# GG-CC1101_v1_2.net
KiCad netlist of a schematic drawn in EAGLE
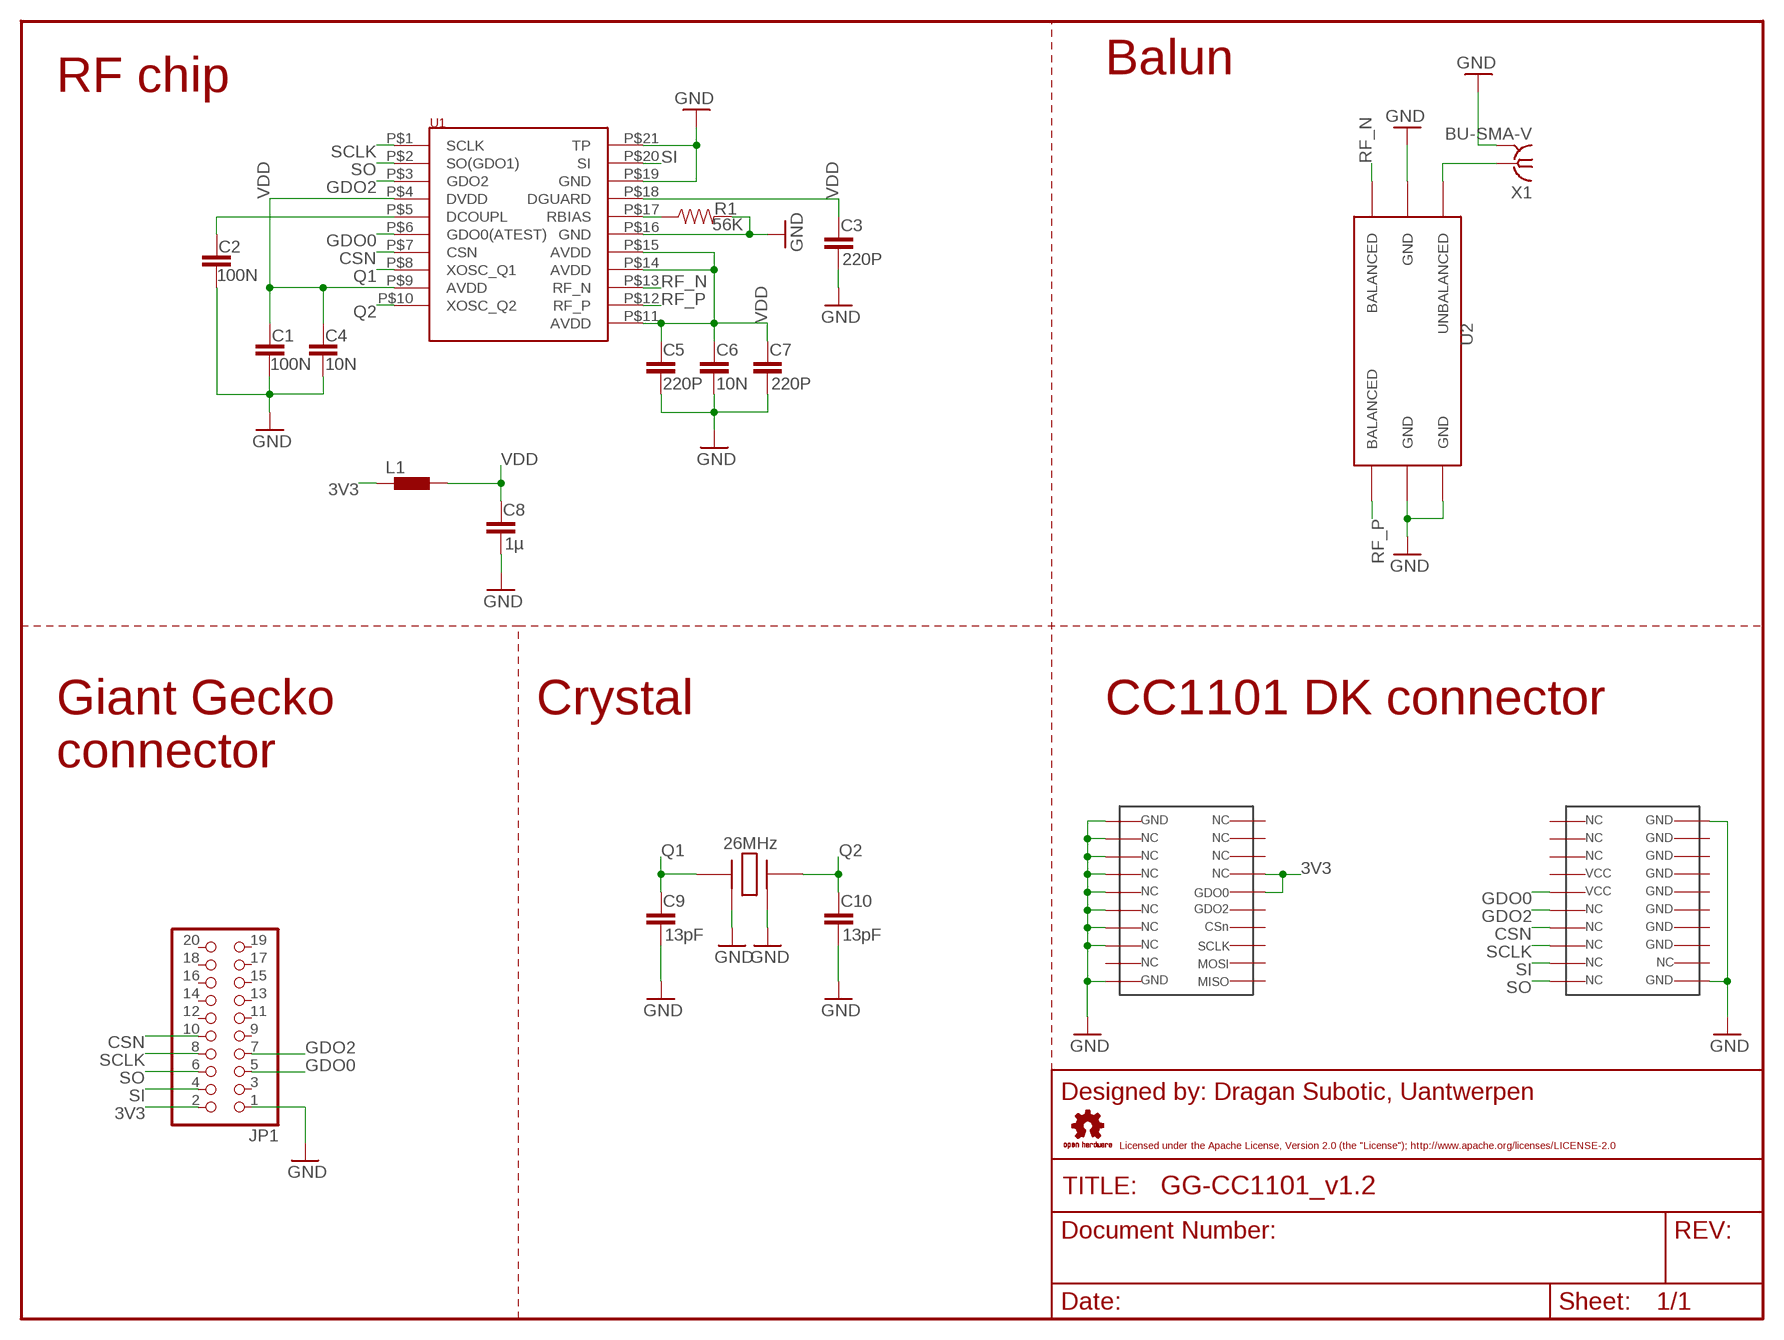
[diagram p0: schematic, sheet 1]

(export (version "E")
  (design (tool "Eeschema 10.0.6"))
  (components
    (comp (ref "C1")
      (value "100N")
      (footprint "eagle-import:0805")
      (libsource (lib "eagle-import") (part "CAP0805"))
    )
    (comp (ref "C2")
      (value "100N")
      (footprint "eagle-import:0805")
      (libsource (lib "eagle-import") (part "CAP0805"))
    )
    (comp (ref "C3")
      (value "220P")
      (footprint "eagle-import:0805")
      (libsource (lib "eagle-import") (part "CAP0805"))
    )
    (comp (ref "C4")
      (value "10N")
      (footprint "eagle-import:0805")
      (libsource (lib "eagle-import") (part "CAP0805"))
    )
    (comp (ref "C5")
      (value "220P")
      (footprint "eagle-import:0805")
      (libsource (lib "eagle-import") (part "CAP0805"))
    )
    (comp (ref "C6")
      (value "10N")
      (footprint "eagle-import:0805")
      (libsource (lib "eagle-import") (part "CAP0805"))
    )
    (comp (ref "C7")
      (value "220P")
      (footprint "eagle-import:0805")
      (libsource (lib "eagle-import") (part "CAP0805"))
    )
    (comp (ref "C8")
      (value "1µ")
      (footprint "eagle-import:0805")
      (libsource (lib "eagle-import") (part "CAP0805"))
    )
    (comp (ref "C9")
      (value "13pF")
      (footprint "eagle-import:0805")
      (libsource (lib "eagle-import") (part "CAP0805"))
    )
    (comp (ref "C10")
      (value "13pF")
      (footprint "eagle-import:0805")
      (libsource (lib "eagle-import") (part "CAP0805"))
    )
    (comp (ref "JP1")
      (value "PINHD-2X10")
      (footprint "eagle-import:2X10")
      (libsource (lib "eagle-import") (part "PINHD-2X10"))
    )
    (comp (ref "L1")
      (value "BLM15HG102SN1")
      (footprint "eagle-import:0402")
      (libsource (lib "eagle-import") (part "BLM15HG102SN1"))
    )
    (comp (ref "Q1")
      (value "XTAL-26MHZ")
      (footprint "eagle-import:XTAL-26MHZ")
      (libsource (lib "eagle-import") (part "XTAL-26MHZ"))
    )
    (comp (ref "R1")
      (value "56K")
      (footprint "eagle-import:0805")
      (libsource (lib "eagle-import") (part "RESISTOR0805-RES"))
    )
    (comp (ref "U$1")
      (value "CC1101-EVAL_KIT")
      (footprint "eagle-import:CC1101-EVAL_KIT")
      (libsource (lib "eagle-import") (part "CC1101-EVAL_KIT"))
    )
    (comp (ref "U1")
      (value "CC1101")
      (footprint "eagle-import:CC1101")
      (libsource (lib "eagle-import") (part "CC1101"))
    )
    (comp (ref "U2")
      (value "BALUN-433MHZ")
      (footprint "eagle-import:BALUN-433MHZ")
      (libsource (lib "eagle-import") (part "BALUN-433MHZ"))
    )
    (comp (ref "X1")
      (value "BU-SMA-V")
      (footprint "eagle-import:BU-SMA-V")
      (libsource (lib "eagle-import") (part "BU-SMA-V"))
    )
  )
  (nets
    (net (code "1") (name "/3V3") (class "Default")
      (node (ref "JP1") (pin "2") (pinfunction "2_2") (pintype "passive"))
      (node (ref "L1") (pin "1") (pinfunction "1_1") (pintype "passive"))
      (node (ref "U$1") (pin "P$14") (pinfunction "P$14_P$14") (pintype "bidirectional"))
      (node (ref "U$1") (pin "P$15") (pinfunction "P$15_P$15") (pintype "bidirectional"))
    )
    (net (code "2") (name "/CSN") (class "Default")
      (node (ref "JP1") (pin "10") (pinfunction "10_10") (pintype "passive"))
      (node (ref "U$1") (pin "P$24") (pinfunction "P$24_P$24") (pintype "bidirectional"))
      (node (ref "U1") (pin "P$7") (pinfunction "CSN_P$7") (pintype "bidirectional"))
    )
    (net (code "3") (name "/GDO0") (class "Default")
      (node (ref "JP1") (pin "5") (pinfunction "5_5") (pintype "passive"))
      (node (ref "U$1") (pin "P$26") (pinfunction "P$26_P$26") (pintype "bidirectional"))
      (node (ref "U1") (pin "P$6") (pinfunction "GDO0(ATEST)_P$6") (pintype "bidirectional"))
    )
    (net (code "4") (name "/GDO2") (class "Default")
      (node (ref "JP1") (pin "7") (pinfunction "7_7") (pintype "passive"))
      (node (ref "U$1") (pin "P$25") (pinfunction "P$25_P$25") (pintype "bidirectional"))
      (node (ref "U1") (pin "P$3") (pinfunction "GDO2_P$3") (pintype "bidirectional"))
    )
    (net (code "5") (name "/Q1") (class "Default")
      (node (ref "C9") (pin "1") (pinfunction "1_1") (pintype "passive"))
      (node (ref "Q1") (pin "P$1") (pinfunction "P$1_P$1") (pintype "bidirectional"))
      (node (ref "U1") (pin "P$8") (pinfunction "XOSC_Q1_P$8") (pintype "bidirectional"))
    )
    (net (code "6") (name "/Q2") (class "Default")
      (node (ref "C10") (pin "1") (pinfunction "1_1") (pintype "passive"))
      (node (ref "Q1") (pin "P$3") (pinfunction "P$3_P$3") (pintype "bidirectional"))
      (node (ref "U1") (pin "P$10") (pinfunction "XOSC_Q2_P$10") (pintype "bidirectional"))
    )
    (net (code "7") (name "/RF_N") (class "Default")
      (node (ref "U1") (pin "P$13") (pinfunction "RF_N_P$13") (pintype "bidirectional"))
      (node (ref "U2") (pin "P$3") (pinfunction "BALANCED_P$3") (pintype "bidirectional"))
    )
    (net (code "8") (name "/RF_P") (class "Default")
      (node (ref "U1") (pin "P$12") (pinfunction "RF_P_P$12") (pintype "bidirectional"))
      (node (ref "U2") (pin "P$4") (pinfunction "BALANCED_P$4") (pintype "bidirectional"))
    )
    (net (code "9") (name "/SCLK") (class "Default")
      (node (ref "JP1") (pin "8") (pinfunction "8_8") (pintype "passive"))
      (node (ref "U$1") (pin "P$23") (pinfunction "P$23_P$23") (pintype "bidirectional"))
      (node (ref "U1") (pin "P$1") (pinfunction "SCLK_P$1") (pintype "bidirectional"))
    )
    (net (code "10") (name "/SI") (class "Default")
      (node (ref "JP1") (pin "4") (pinfunction "4_4") (pintype "passive"))
      (node (ref "U$1") (pin "P$22") (pinfunction "P$22_P$22") (pintype "bidirectional"))
      (node (ref "U1") (pin "P$20") (pinfunction "SI_P$20") (pintype "bidirectional"))
    )
    (net (code "11") (name "/SO") (class "Default")
      (node (ref "JP1") (pin "6") (pinfunction "6_6") (pintype "passive"))
      (node (ref "U$1") (pin "P$21") (pinfunction "P$21_P$21") (pintype "bidirectional"))
      (node (ref "U1") (pin "P$2") (pinfunction "SO(GDO1)_P$2") (pintype "bidirectional"))
    )
    (net (code "12") (name "/VDD") (class "Default")
      (node (ref "C1") (pin "1") (pinfunction "1_1") (pintype "passive"))
      (node (ref "C3") (pin "1") (pinfunction "1_1") (pintype "passive"))
      (node (ref "C4") (pin "1") (pinfunction "1_1") (pintype "passive"))
      (node (ref "C5") (pin "1") (pinfunction "1_1") (pintype "passive"))
      (node (ref "C6") (pin "1") (pinfunction "1_1") (pintype "passive"))
      (node (ref "C7") (pin "1") (pinfunction "1_1") (pintype "passive"))
      (node (ref "C8") (pin "1") (pinfunction "1_1") (pintype "passive"))
      (node (ref "L1") (pin "2") (pinfunction "2_2") (pintype "passive"))
      (node (ref "U1") (pin "P$11") (pinfunction "AVDD_P$11") (pintype "bidirectional"))
      (node (ref "U1") (pin "P$14") (pinfunction "AVDD_P$14") (pintype "bidirectional"))
      (node (ref "U1") (pin "P$15") (pinfunction "AVDD_P$15") (pintype "bidirectional"))
      (node (ref "U1") (pin "P$18") (pinfunction "DGUARD_P$18") (pintype "bidirectional"))
      (node (ref "U1") (pin "P$4") (pinfunction "DVDD_P$4") (pintype "bidirectional"))
      (node (ref "U1") (pin "P$9") (pinfunction "AVDD_P$9") (pintype "bidirectional"))
    )
    (net (code "13") (name "GND") (class "Default")
      (node (ref "C1") (pin "2") (pinfunction "2_2") (pintype "passive"))
      (node (ref "C10") (pin "2") (pinfunction "2_2") (pintype "passive"))
      (node (ref "C2") (pin "2") (pinfunction "2_2") (pintype "passive"))
      (node (ref "C3") (pin "2") (pinfunction "2_2") (pintype "passive"))
      (node (ref "C4") (pin "2") (pinfunction "2_2") (pintype "passive"))
      (node (ref "C5") (pin "2") (pinfunction "2_2") (pintype "passive"))
      (node (ref "C6") (pin "2") (pinfunction "2_2") (pintype "passive"))
      (node (ref "C7") (pin "2") (pinfunction "2_2") (pintype "passive"))
      (node (ref "C8") (pin "2") (pinfunction "2_2") (pintype "passive"))
      (node (ref "C9") (pin "2") (pinfunction "2_2") (pintype "passive"))
      (node (ref "JP1") (pin "1") (pinfunction "1_1") (pintype "passive"))
      (node (ref "Q1") (pin "P$2") (pinfunction "P$2_P$2") (pintype "bidirectional"))
      (node (ref "Q1") (pin "P$4") (pinfunction "P$4_P$4") (pintype "bidirectional"))
      (node (ref "R1") (pin "2") (pinfunction "2_2") (pintype "passive"))
      (node (ref "U$1") (pin "P$1") (pinfunction "P$1_P$1") (pintype "bidirectional"))
      (node (ref "U$1") (pin "P$10") (pinfunction "P$10_P$10") (pintype "bidirectional"))
      (node (ref "U$1") (pin "P$3") (pinfunction "P$3_P$3") (pintype "bidirectional"))
      (node (ref "U$1") (pin "P$31") (pinfunction "P$31_P$31") (pintype "bidirectional"))
      (node (ref "U$1") (pin "P$4") (pinfunction "P$4_P$4") (pintype "bidirectional"))
      (node (ref "U$1") (pin "P$40") (pinfunction "P$40_P$40") (pintype "bidirectional"))
      (node (ref "U$1") (pin "P$5") (pinfunction "P$5_P$5") (pintype "bidirectional"))
      (node (ref "U$1") (pin "P$6") (pinfunction "P$6_P$6") (pintype "bidirectional"))
      (node (ref "U$1") (pin "P$7") (pinfunction "P$7_P$7") (pintype "bidirectional"))
      (node (ref "U$1") (pin "P$8") (pinfunction "P$8_P$8") (pintype "bidirectional"))
      (node (ref "U$1") (pin "P$9") (pinfunction "P$9_P$9") (pintype "bidirectional"))
      (node (ref "U1") (pin "P$16") (pinfunction "GND_P$16") (pintype "bidirectional"))
      (node (ref "U1") (pin "P$19") (pinfunction "GND_P$19") (pintype "bidirectional"))
      (node (ref "U1") (pin "P$21") (pinfunction "TP_P$21") (pintype "bidirectional"))
      (node (ref "U2") (pin "P$2") (pinfunction "GND_P$2") (pintype "bidirectional"))
      (node (ref "U2") (pin "P$5") (pinfunction "GND_P$5") (pintype "bidirectional"))
      (node (ref "U2") (pin "P$6") (pinfunction "GND_P$6") (pintype "bidirectional"))
      (node (ref "X1") (pin "2") (pinfunction "2_2") (pintype "passive"))
      (node (ref "X1") (pin "3") (pinfunction "2_3") (pintype "passive"))
      (node (ref "X1") (pin "4") (pinfunction "2_4") (pintype "passive"))
      (node (ref "X1") (pin "5") (pinfunction "2_5") (pintype "passive"))
    )
    (net (code "14") (name "Net-(U1-DCOUPL)") (class "Default")
      (node (ref "C2") (pin "1") (pinfunction "1_1") (pintype "passive"))
      (node (ref "U1") (pin "P$5") (pinfunction "DCOUPL_P$5") (pintype "bidirectional"))
    )
    (net (code "15") (name "Net-(U1-RBIAS)") (class "Default")
      (node (ref "R1") (pin "1") (pinfunction "1_1") (pintype "passive"))
      (node (ref "U1") (pin "P$17") (pinfunction "RBIAS_P$17") (pintype "bidirectional"))
    )
    (net (code "16") (name "Net-(U2-UNBALANCED)") (class "Default")
      (node (ref "U2") (pin "P$1") (pinfunction "UNBALANCED_P$1") (pintype "bidirectional"))
      (node (ref "X1") (pin "1") (pinfunction "1_1") (pintype "passive"))
    )
    (net (code "17") (name "unconnected-(JP1-Pad3)") (class "Default")
      (node (ref "JP1") (pin "3") (pinfunction "3_3") (pintype "passive"))
    )
    (net (code "18") (name "unconnected-(JP1-Pad9)") (class "Default")
      (node (ref "JP1") (pin "9") (pinfunction "9_9") (pintype "passive"))
    )
    (net (code "19") (name "unconnected-(JP1-Pad11)") (class "Default")
      (node (ref "JP1") (pin "11") (pinfunction "11_11") (pintype "passive"))
    )
    (net (code "20") (name "unconnected-(JP1-Pad12)") (class "Default")
      (node (ref "JP1") (pin "12") (pinfunction "12_12") (pintype "passive"))
    )
    (net (code "21") (name "unconnected-(JP1-Pad13)") (class "Default")
      (node (ref "JP1") (pin "13") (pinfunction "13_13") (pintype "passive"))
    )
    (net (code "22") (name "unconnected-(JP1-Pad14)") (class "Default")
      (node (ref "JP1") (pin "14") (pinfunction "14_14") (pintype "passive"))
    )
    (net (code "23") (name "unconnected-(JP1-Pad15)") (class "Default")
      (node (ref "JP1") (pin "15") (pinfunction "15_15") (pintype "passive"))
    )
    (net (code "24") (name "unconnected-(JP1-Pad16)") (class "Default")
      (node (ref "JP1") (pin "16") (pinfunction "16_16") (pintype "passive"))
    )
    (net (code "25") (name "unconnected-(JP1-Pad17)") (class "Default")
      (node (ref "JP1") (pin "17") (pinfunction "17_17") (pintype "passive"))
    )
    (net (code "26") (name "unconnected-(JP1-Pad18)") (class "Default")
      (node (ref "JP1") (pin "18") (pinfunction "18_18") (pintype "passive"))
    )
    (net (code "27") (name "unconnected-(JP1-Pad19)") (class "Default")
      (node (ref "JP1") (pin "19") (pinfunction "19_19") (pintype "passive"))
    )
    (net (code "28") (name "unconnected-(JP1-Pad20)") (class "Default")
      (node (ref "JP1") (pin "20") (pinfunction "20_20") (pintype "passive"))
    )
    (net (code "29") (name "unconnected-(U$1-PadP$2)") (class "Default")
      (node (ref "U$1") (pin "P$2") (pinfunction "P$2_P$2") (pintype "bidirectional"))
    )
    (net (code "30") (name "unconnected-(U$1-PadP$11)") (class "Default")
      (node (ref "U$1") (pin "P$11") (pinfunction "P$11_P$11") (pintype "bidirectional"))
    )
    (net (code "31") (name "unconnected-(U$1-PadP$12)") (class "Default")
      (node (ref "U$1") (pin "P$12") (pinfunction "P$12_P$12") (pintype "bidirectional"))
    )
    (net (code "32") (name "unconnected-(U$1-PadP$13)") (class "Default")
      (node (ref "U$1") (pin "P$13") (pinfunction "P$13_P$13") (pintype "bidirectional"))
    )
    (net (code "33") (name "unconnected-(U$1-PadP$16)") (class "Default")
      (node (ref "U$1") (pin "P$16") (pinfunction "P$16_P$16") (pintype "bidirectional"))
    )
    (net (code "34") (name "unconnected-(U$1-PadP$17)") (class "Default")
      (node (ref "U$1") (pin "P$17") (pinfunction "P$17_P$17") (pintype "bidirectional"))
    )
    (net (code "35") (name "unconnected-(U$1-PadP$18)") (class "Default")
      (node (ref "U$1") (pin "P$18") (pinfunction "P$18_P$18") (pintype "bidirectional"))
    )
    (net (code "36") (name "unconnected-(U$1-PadP$19)") (class "Default")
      (node (ref "U$1") (pin "P$19") (pinfunction "P$19_P$19") (pintype "bidirectional"))
    )
    (net (code "37") (name "unconnected-(U$1-PadP$20)") (class "Default")
      (node (ref "U$1") (pin "P$20") (pinfunction "P$20_P$20") (pintype "bidirectional"))
    )
    (net (code "38") (name "unconnected-(U$1-PadP$27)") (class "Default")
      (node (ref "U$1") (pin "P$27") (pinfunction "P$27_P$27") (pintype "bidirectional"))
    )
    (net (code "39") (name "unconnected-(U$1-PadP$28)") (class "Default")
      (node (ref "U$1") (pin "P$28") (pinfunction "P$28_P$28") (pintype "bidirectional"))
    )
    (net (code "40") (name "unconnected-(U$1-PadP$29)") (class "Default")
      (node (ref "U$1") (pin "P$29") (pinfunction "P$29_P$29") (pintype "bidirectional"))
    )
    (net (code "41") (name "unconnected-(U$1-PadP$30)") (class "Default")
      (node (ref "U$1") (pin "P$30") (pinfunction "P$30_P$30") (pintype "bidirectional"))
    )
    (net (code "42") (name "unconnected-(U$1-PadP$32)") (class "Default")
      (node (ref "U$1") (pin "P$32") (pinfunction "P$32_P$32") (pintype "bidirectional"))
    )
    (net (code "43") (name "unconnected-(U$1-PadP$33)") (class "Default")
      (node (ref "U$1") (pin "P$33") (pinfunction "P$33_P$33") (pintype "bidirectional"))
    )
    (net (code "44") (name "unconnected-(U$1-PadP$34)") (class "Default")
      (node (ref "U$1") (pin "P$34") (pinfunction "P$34_P$34") (pintype "bidirectional"))
    )
    (net (code "45") (name "unconnected-(U$1-PadP$35)") (class "Default")
      (node (ref "U$1") (pin "P$35") (pinfunction "P$35_P$35") (pintype "bidirectional"))
    )
    (net (code "46") (name "unconnected-(U$1-PadP$36)") (class "Default")
      (node (ref "U$1") (pin "P$36") (pinfunction "P$36_P$36") (pintype "bidirectional"))
    )
    (net (code "47") (name "unconnected-(U$1-PadP$37)") (class "Default")
      (node (ref "U$1") (pin "P$37") (pinfunction "P$37_P$37") (pintype "bidirectional"))
    )
    (net (code "48") (name "unconnected-(U$1-PadP$38)") (class "Default")
      (node (ref "U$1") (pin "P$38") (pinfunction "P$38_P$38") (pintype "bidirectional"))
    )
    (net (code "49") (name "unconnected-(U$1-PadP$39)") (class "Default")
      (node (ref "U$1") (pin "P$39") (pinfunction "P$39_P$39") (pintype "bidirectional"))
    )
  )
)
